# smopcb.net
KiCad netlist of a schematic drawn in EasyEDA
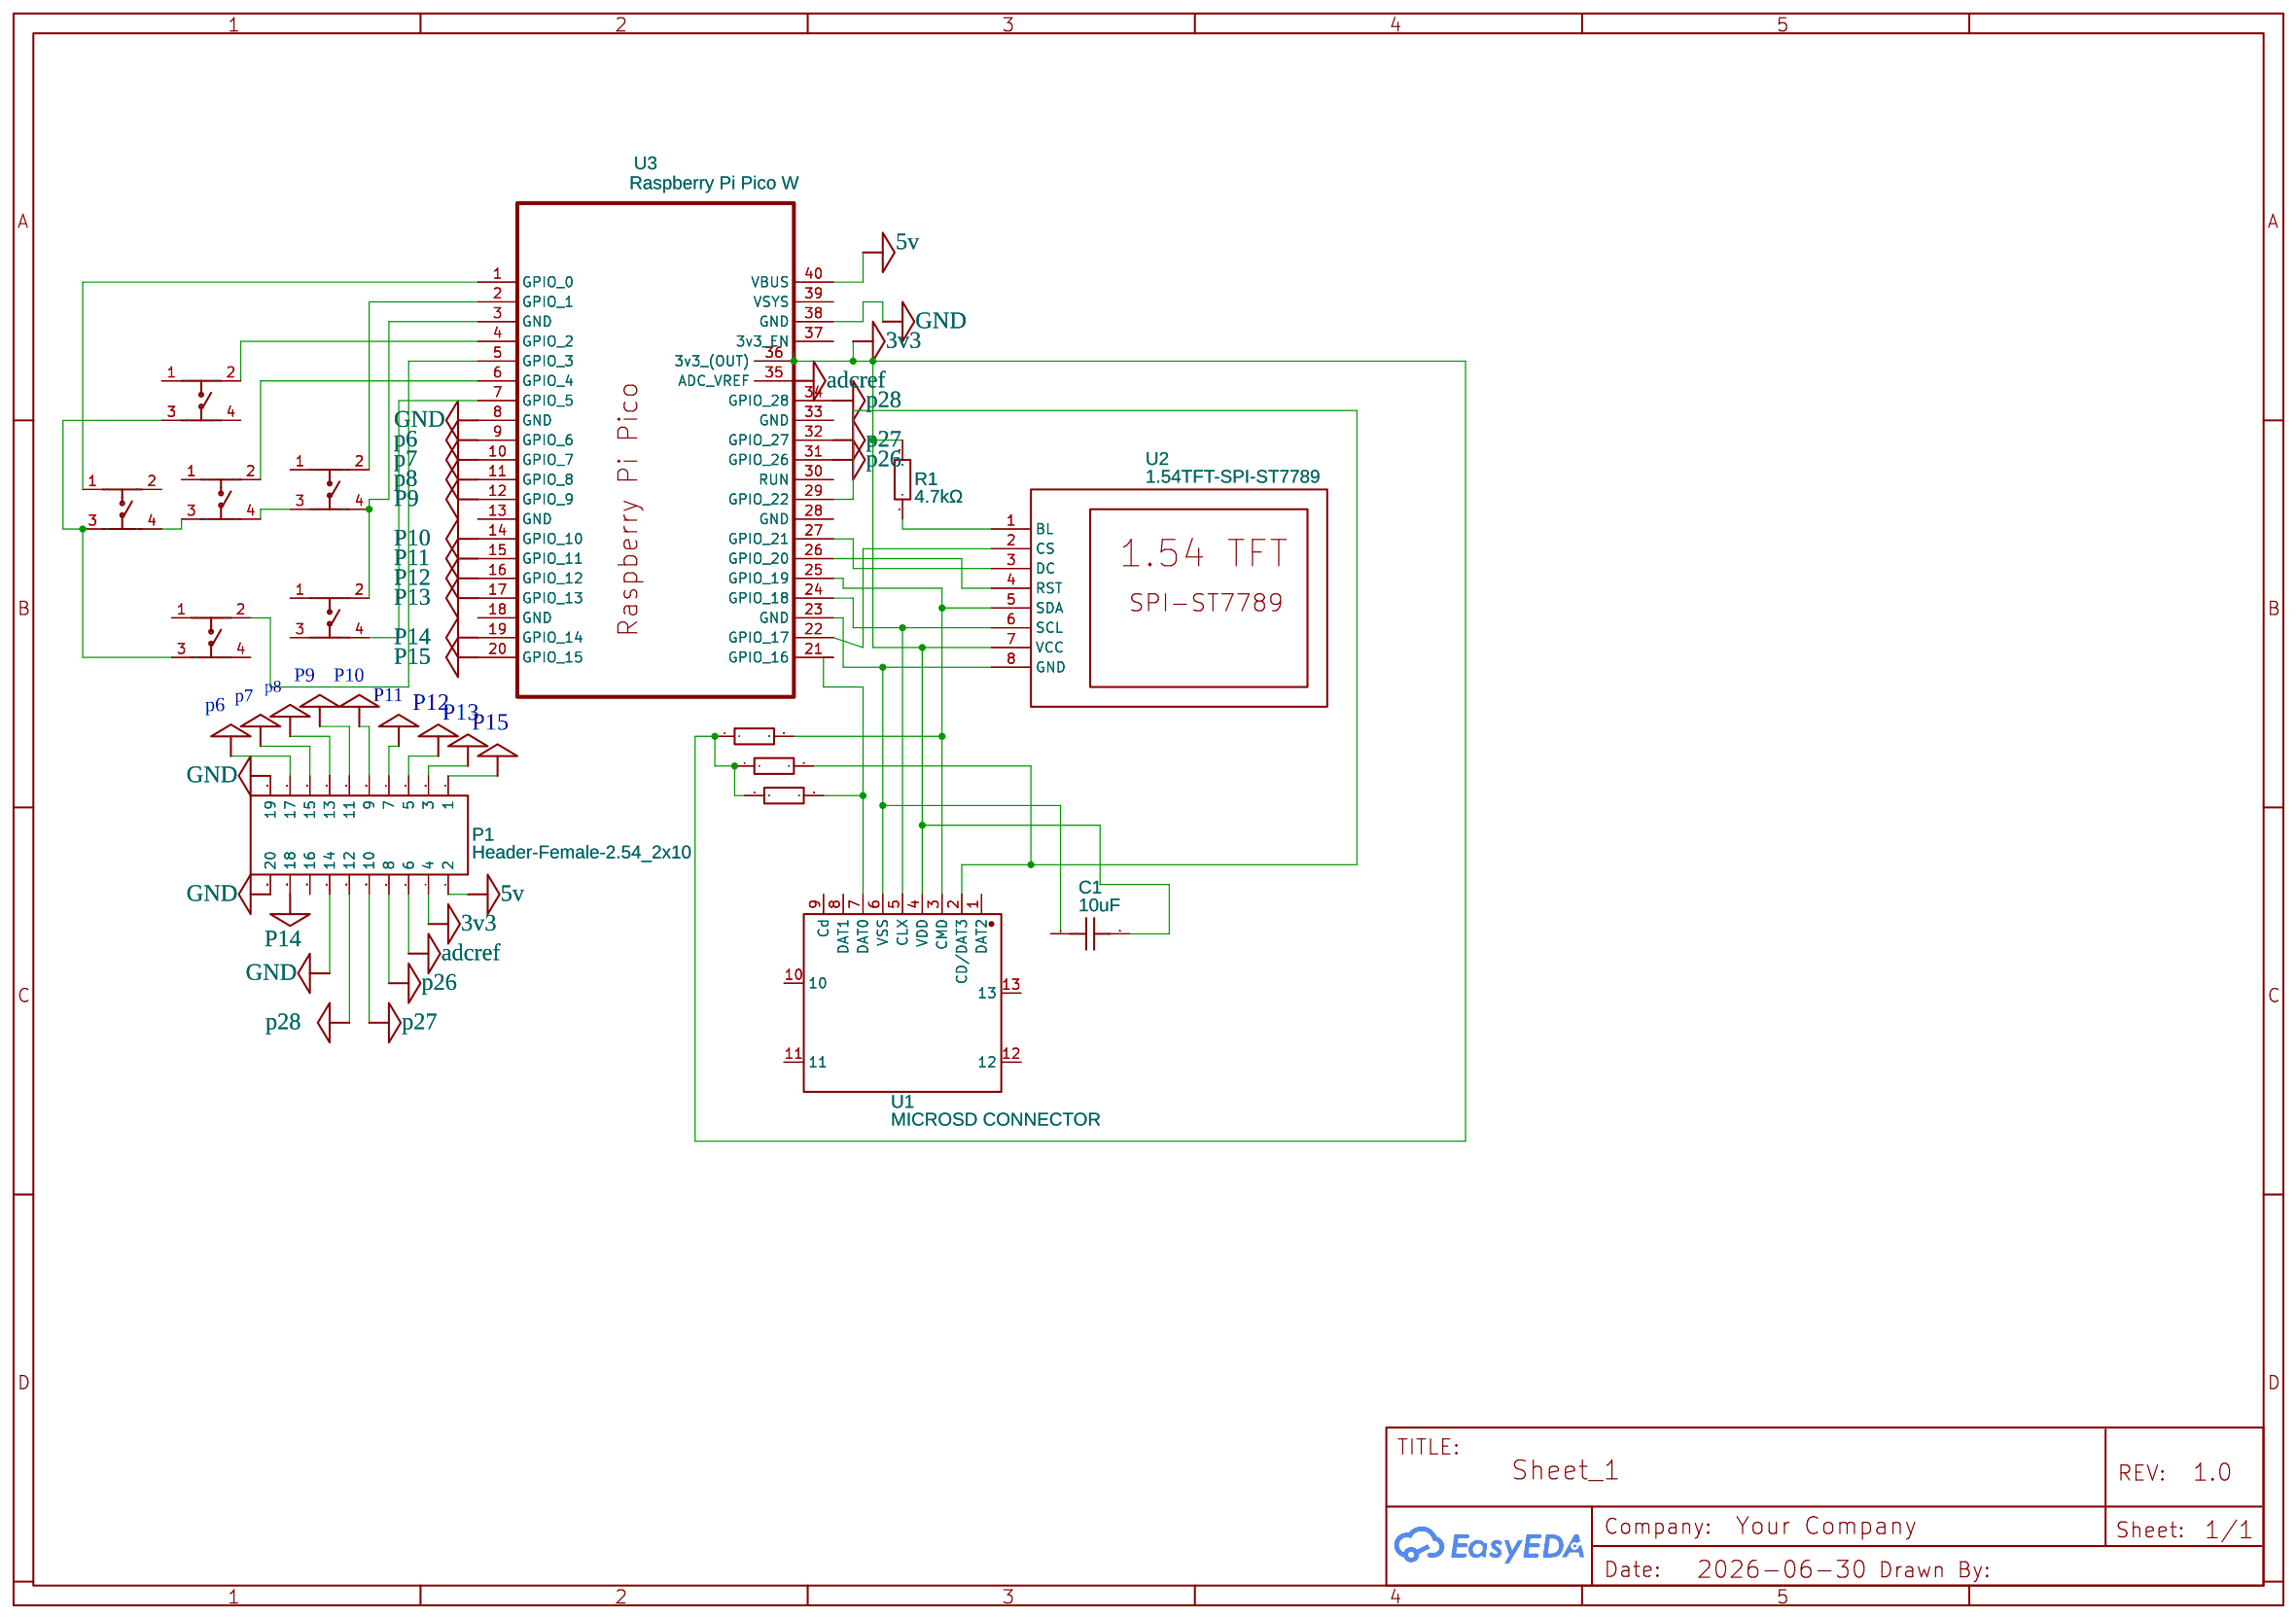
[diagram p0: schematic sheet]

(export (version "E")
  (design (tool "Eeschema 10.0.6"))
  (components
    (comp (ref "C1")
      (value "10uF")
      (fields
        (field (name "Manufacturer Part") "0805X5R106K350NT")
        (field (name "Manufacturer") "AIDE(爱迪电容)")
      )
      (libsource (lib "") (part "0805X5R106K350NT"))
    )
    (comp (ref "KEY1")
      (value "4PINTACTPCBTHTPUSHBUTTON")
      (fields (field (name "Manufacturer Part") "4pinTACTPCBTHTPushButton"))
      (libsource (lib "") (part "4PINTACTPCBTHTPUSHBUTTON"))
    )
    (comp (ref "KEY2")
      (value "4PINTACTPCBTHTPUSHBUTTON")
      (fields (field (name "Manufacturer Part") "4pinTACTPCBTHTPushButton"))
      (libsource (lib "") (part "4PINTACTPCBTHTPUSHBUTTON"))
    )
    (comp (ref "KEY3")
      (value "4PINTACTPCBTHTPUSHBUTTON")
      (fields (field (name "Manufacturer Part") "4pinTACTPCBTHTPushButton"))
      (libsource (lib "") (part "4PINTACTPCBTHTPUSHBUTTON"))
    )
    (comp (ref "KEY4")
      (value "4PINTACTPCBTHTPUSHBUTTON")
      (fields (field (name "Manufacturer Part") "4pinTACTPCBTHTPushButton"))
      (libsource (lib "") (part "4PINTACTPCBTHTPUSHBUTTON"))
    )
    (comp (ref "KEY5")
      (value "4PINTACTPCBTHTPUSHBUTTON")
      (fields (field (name "Manufacturer Part") "4pinTACTPCBTHTPushButton"))
      (libsource (lib "") (part "4PINTACTPCBTHTPUSHBUTTON"))
    )
    (comp (ref "KEY6")
      (value "4PINTACTPCBTHTPUSHBUTTON")
      (fields (field (name "Manufacturer Part") "4pinTACTPCBTHTPushButton"))
      (libsource (lib "") (part "4PINTACTPCBTHTPUSHBUTTON"))
    )
    (comp (ref "P1")
      (value "Header-Female-2.54_2x10")
      (fields (field (name "Manufacturer Part") "2.54-2*10P母") (field (name "Manufacturer") "BOOMELE(博穆精密)"))
      (libsource (lib "") (part "Header-Female-2.54_2x10"))
    )
    (comp (ref "R1")
      (value "4.7kΩ")
      (fields (field (name "Manufacturer Part") "RC0805FR-074K7L") (field (name "Manufacturer") "YAGEO(国巨)"))
      (libsource (lib "") (part "RESISTOR 0805 4K7"))
    )
    (comp (ref "R2")
      (value "4.7kΩ")
      (fields (field (name "Manufacturer Part") "RMC08054.7K1%N") (field (name "Manufacturer") "Tyohm(幸亚电阻)"))
      (libsource (lib "") (part "RMC08054.7K1%N"))
    )
    (comp (ref "R3")
      (value "4.7kΩ")
      (fields (field (name "Manufacturer Part") "RMC08054.7K1%N") (field (name "Manufacturer") "Tyohm(幸亚电阻)"))
      (libsource (lib "") (part "RMC08054.7K1%N"))
    )
    (comp (ref "R4")
      (value "4.7kΩ")
      (fields (field (name "Manufacturer Part") "RMC08054.7K1%N") (field (name "Manufacturer") "Tyohm(幸亚电阻)"))
      (libsource (lib "") (part "RMC08054.7K1%N"))
    )
    (comp (ref "U1")
      (value "MICROSD CONNECTOR")
      (fields (field (name "Manufacturer Part") "CQMicro_SDCARD_CQ036_HMA19PSMT"))
      (libsource (lib "") (part "MICROSD CONNECTOR"))
    )
    (comp (ref "U2") (value "1.54TFT-SPI-ST7789") (libsource (lib "") (part "1.54TFT-SPI-ST7789")))
    (comp (ref "U3") (value "Raspberry Pi Pico W") (libsource (lib "") (part "Raspberry Pi Pico W")))
  )
  (nets
    (net (code "1") (name "3v3") (class "Default")
      (node (ref "C1") (pin "2") (pinfunction "2_2") (pintype "unspecified"))
      (node (ref "P1") (pin "4") (pinfunction "4_4") (pintype "input"))
      (node (ref "R1") (pin "2") (pinfunction "2_2") (pintype "input"))
      (node (ref "R2") (pin "1") (pinfunction "1_1") (pintype "unspecified"))
      (node (ref "R3") (pin "1") (pinfunction "1_1") (pintype "unspecified"))
      (node (ref "R4") (pin "1") (pinfunction "1_1") (pintype "unspecified"))
      (node (ref "U1") (pin "4") (pinfunction "VDD_4") (pintype "unspecified"))
      (node (ref "U2") (pin "7") (pinfunction "VCC_7") (pintype "unspecified"))
      (node (ref "U3") (pin "36") (pinfunction "3v3_(OUT)_36") (pintype "unspecified"))
    )
    (net (code "2") (name "5v") (class "Default")
      (node (ref "P1") (pin "2") (pinfunction "2_2") (pintype "input"))
      (node (ref "U3") (pin "40") (pinfunction "VBUS_40") (pintype "unspecified"))
    )
    (net (code "3") (name "GND") (class "Default")
      (node (ref "P1") (pin "14") (pinfunction "14_14") (pintype "input"))
      (node (ref "P1") (pin "19") (pinfunction "19_19") (pintype "input"))
      (node (ref "P1") (pin "20") (pinfunction "20_20") (pintype "input"))
      (node (ref "U3") (pin "38") (pinfunction "GND_38") (pintype "unspecified"))
      (node (ref "U3") (pin "8") (pinfunction "GND_8") (pintype "unspecified"))
    )
    (net (code "4") (name "Net-(KEY1-Pad3)") (class "Default")
      (node (ref "KEY1") (pin "3") (pinfunction "3_3") (pintype "unspecified"))
      (node (ref "KEY2") (pin "3") (pinfunction "3_3") (pintype "unspecified"))
      (node (ref "KEY3") (pin "3") (pinfunction "3_3") (pintype "unspecified"))
    )
    (net (code "5") (name "Net-(KEY3-Pad4)") (class "Default")
      (node (ref "KEY3") (pin "4") (pinfunction "4_4") (pintype "unspecified"))
      (node (ref "KEY5") (pin "3") (pinfunction "3_3") (pintype "unspecified"))
    )
    (net (code "6") (name "Net-(KEY4-Pad3)") (class "Default")
      (node (ref "KEY4") (pin "3") (pinfunction "3_3") (pintype "unspecified"))
      (node (ref "KEY5") (pin "4") (pinfunction "4_4") (pintype "unspecified"))
    )
    (net (code "7") (name "Net-(KEY4-Pad4)") (class "Default")
      (node (ref "KEY4") (pin "4") (pinfunction "4_4") (pintype "unspecified"))
      (node (ref "KEY6") (pin "2") (pinfunction "2_2") (pintype "unspecified"))
      (node (ref "U3") (pin "3") (pinfunction "GND_3") (pintype "unspecified"))
    )
    (net (code "8") (name "Net-(U1-CD{slash}DAT3)") (class "Default")
      (node (ref "R2") (pin "2") (pinfunction "2_2") (pintype "unspecified"))
      (node (ref "U1") (pin "2") (pinfunction "CD/DAT3_2") (pintype "unspecified"))
      (node (ref "U3") (pin "29") (pinfunction "GPIO_22_29") (pintype "unspecified"))
    )
    (net (code "9") (name "Net-(U1-CLX)") (class "Default")
      (node (ref "U1") (pin "5") (pinfunction "CLX_5") (pintype "unspecified"))
      (node (ref "U2") (pin "6") (pinfunction "SCL_6") (pintype "unspecified"))
      (node (ref "U3") (pin "24") (pinfunction "GPIO_18_24") (pintype "unspecified"))
    )
    (net (code "10") (name "Net-(U1-CMD)") (class "Default")
      (node (ref "R4") (pin "2") (pinfunction "2_2") (pintype "unspecified"))
      (node (ref "U1") (pin "3") (pinfunction "CMD_3") (pintype "unspecified"))
      (node (ref "U2") (pin "5") (pinfunction "SDA_5") (pintype "unspecified"))
      (node (ref "U3") (pin "25") (pinfunction "GPIO_19_25") (pintype "unspecified"))
    )
    (net (code "11") (name "Net-(U1-DAT0)") (class "Default")
      (node (ref "R3") (pin "2") (pinfunction "2_2") (pintype "unspecified"))
      (node (ref "U1") (pin "7") (pinfunction "DAT0_7") (pintype "unspecified"))
      (node (ref "U3") (pin "21") (pinfunction "GPIO_16_21") (pintype "unspecified"))
    )
    (net (code "12") (name "Net-(U1-VSS)") (class "Default")
      (node (ref "C1") (pin "1") (pinfunction "1_1") (pintype "unspecified"))
      (node (ref "U1") (pin "6") (pinfunction "VSS_6") (pintype "unspecified"))
      (node (ref "U2") (pin "8") (pinfunction "GND_8") (pintype "unspecified"))
      (node (ref "U3") (pin "23") (pinfunction "GND_23") (pintype "unspecified"))
    )
    (net (code "13") (name "Net-(U2-BL)") (class "Default")
      (node (ref "R1") (pin "1") (pinfunction "1_1") (pintype "input"))
      (node (ref "U2") (pin "1") (pinfunction "BL_1") (pintype "unspecified"))
    )
    (net (code "14") (name "Net-(U2-CS)") (class "Default")
      (node (ref "U2") (pin "2") (pinfunction "CS_2") (pintype "unspecified"))
      (node (ref "U3") (pin "22") (pinfunction "GPIO_17_22") (pintype "unspecified"))
    )
    (net (code "15") (name "Net-(U2-DC)") (class "Default")
      (node (ref "U2") (pin "3") (pinfunction "DC_3") (pintype "unspecified"))
      (node (ref "U3") (pin "27") (pinfunction "GPIO_21_27") (pintype "unspecified"))
    )
    (net (code "16") (name "Net-(U2-RST)") (class "Default")
      (node (ref "U2") (pin "4") (pinfunction "RST_4") (pintype "unspecified"))
      (node (ref "U3") (pin "26") (pinfunction "GPIO_20_26") (pintype "unspecified"))
    )
    (net (code "17") (name "Net-(U3-GPIO_0)") (class "Default")
      (node (ref "KEY3") (pin "1") (pinfunction "1_1") (pintype "unspecified"))
      (node (ref "U3") (pin "1") (pinfunction "GPIO_0_1") (pintype "unspecified"))
    )
    (net (code "18") (name "Net-(U3-GPIO_1)") (class "Default")
      (node (ref "KEY4") (pin "2") (pinfunction "2_2") (pintype "unspecified"))
      (node (ref "U3") (pin "2") (pinfunction "GPIO_1_2") (pintype "unspecified"))
    )
    (net (code "19") (name "Net-(U3-GPIO_2)") (class "Default")
      (node (ref "KEY1") (pin "2") (pinfunction "2_2") (pintype "unspecified"))
      (node (ref "U3") (pin "4") (pinfunction "GPIO_2_4") (pintype "unspecified"))
    )
    (net (code "20") (name "Net-(U3-GPIO_3)") (class "Default")
      (node (ref "KEY2") (pin "2") (pinfunction "2_2") (pintype "unspecified"))
      (node (ref "U3") (pin "5") (pinfunction "GPIO_3_5") (pintype "unspecified"))
    )
    (net (code "21") (name "Net-(U3-GPIO_4)") (class "Default")
      (node (ref "KEY5") (pin "2") (pinfunction "2_2") (pintype "unspecified"))
      (node (ref "U3") (pin "6") (pinfunction "GPIO_4_6") (pintype "unspecified"))
    )
    (net (code "22") (name "Net-(U3-GPIO_5)") (class "Default")
      (node (ref "KEY6") (pin "4") (pinfunction "4_4") (pintype "unspecified"))
      (node (ref "U3") (pin "7") (pinfunction "GPIO_5_7") (pintype "unspecified"))
    )
    (net (code "23") (name "P9") (class "Default")
      (node (ref "P1") (pin "11") (pinfunction "11_11") (pintype "input"))
      (node (ref "U3") (pin "12") (pinfunction "GPIO_9_12") (pintype "unspecified"))
    )
    (net (code "24") (name "P10") (class "Default")
      (node (ref "P1") (pin "9") (pinfunction "9_9") (pintype "input"))
      (node (ref "U3") (pin "14") (pinfunction "GPIO_10_14") (pintype "unspecified"))
    )
    (net (code "25") (name "P11") (class "Default")
      (node (ref "P1") (pin "7") (pinfunction "7_7") (pintype "input"))
      (node (ref "U3") (pin "15") (pinfunction "GPIO_11_15") (pintype "unspecified"))
    )
    (net (code "26") (name "P12") (class "Default")
      (node (ref "P1") (pin "5") (pinfunction "5_5") (pintype "input"))
      (node (ref "U3") (pin "16") (pinfunction "GPIO_12_16") (pintype "unspecified"))
    )
    (net (code "27") (name "P13") (class "Default")
      (node (ref "P1") (pin "3") (pinfunction "3_3") (pintype "input"))
      (node (ref "U3") (pin "17") (pinfunction "GPIO_13_17") (pintype "unspecified"))
    )
    (net (code "28") (name "P14") (class "Default")
      (node (ref "P1") (pin "18") (pinfunction "18_18") (pintype "input"))
      (node (ref "U3") (pin "19") (pinfunction "GPIO_14_19") (pintype "unspecified"))
    )
    (net (code "29") (name "P15") (class "Default")
      (node (ref "P1") (pin "1") (pinfunction "1_1") (pintype "input"))
      (node (ref "U3") (pin "20") (pinfunction "GPIO_15_20") (pintype "unspecified"))
    )
    (net (code "30") (name "adcref") (class "Default")
      (node (ref "P1") (pin "6") (pinfunction "6_6") (pintype "input"))
      (node (ref "U3") (pin "35") (pinfunction "ADC_VREF_35") (pintype "unspecified"))
    )
    (net (code "31") (name "p6") (class "Default")
      (node (ref "P1") (pin "17") (pinfunction "17_17") (pintype "input"))
      (node (ref "U3") (pin "9") (pinfunction "GPIO_6_9") (pintype "unspecified"))
    )
    (net (code "32") (name "p7") (class "Default")
      (node (ref "P1") (pin "15") (pinfunction "15_15") (pintype "input"))
      (node (ref "U3") (pin "10") (pinfunction "GPIO_7_10") (pintype "unspecified"))
    )
    (net (code "33") (name "p8") (class "Default")
      (node (ref "P1") (pin "13") (pinfunction "13_13") (pintype "input"))
      (node (ref "U3") (pin "11") (pinfunction "GPIO_8_11") (pintype "unspecified"))
    )
    (net (code "34") (name "p26") (class "Default")
      (node (ref "P1") (pin "8") (pinfunction "8_8") (pintype "input"))
      (node (ref "U3") (pin "31") (pinfunction "GPIO_26_31") (pintype "unspecified"))
    )
    (net (code "35") (name "p27") (class "Default")
      (node (ref "P1") (pin "10") (pinfunction "10_10") (pintype "input"))
      (node (ref "U3") (pin "32") (pinfunction "GPIO_27_32") (pintype "unspecified"))
    )
    (net (code "36") (name "p28") (class "Default")
      (node (ref "P1") (pin "12") (pinfunction "12_12") (pintype "input"))
      (node (ref "U3") (pin "34") (pinfunction "GPIO_28_34") (pintype "unspecified"))
    )
    (net (code "37") (name "unconnected-(KEY1-Pad1)") (class "Default")
      (node (ref "KEY1") (pin "1") (pinfunction "1_1") (pintype "unspecified"))
    )
    (net (code "38") (name "unconnected-(KEY1-Pad4)") (class "Default")
      (node (ref "KEY1") (pin "4") (pinfunction "4_4") (pintype "unspecified"))
    )
    (net (code "39") (name "unconnected-(KEY2-Pad1)") (class "Default")
      (node (ref "KEY2") (pin "1") (pinfunction "1_1") (pintype "unspecified"))
    )
    (net (code "40") (name "unconnected-(KEY2-Pad4)") (class "Default")
      (node (ref "KEY2") (pin "4") (pinfunction "4_4") (pintype "unspecified"))
    )
    (net (code "41") (name "unconnected-(KEY3-Pad2)") (class "Default")
      (node (ref "KEY3") (pin "2") (pinfunction "2_2") (pintype "unspecified"))
    )
    (net (code "42") (name "unconnected-(KEY4-Pad1)") (class "Default")
      (node (ref "KEY4") (pin "1") (pinfunction "1_1") (pintype "unspecified"))
    )
    (net (code "43") (name "unconnected-(KEY5-Pad1)") (class "Default")
      (node (ref "KEY5") (pin "1") (pinfunction "1_1") (pintype "unspecified"))
    )
    (net (code "44") (name "unconnected-(KEY6-Pad1)") (class "Default")
      (node (ref "KEY6") (pin "1") (pinfunction "1_1") (pintype "unspecified"))
    )
    (net (code "45") (name "unconnected-(KEY6-Pad3)") (class "Default")
      (node (ref "KEY6") (pin "3") (pinfunction "3_3") (pintype "unspecified"))
    )
    (net (code "46") (name "unconnected-(P1-Pad16)") (class "Default")
      (node (ref "P1") (pin "16") (pinfunction "16_16") (pintype "input"))
    )
    (net (code "47") (name "unconnected-(U1-Cd-Pad9)") (class "Default")
      (node (ref "U1") (pin "9") (pinfunction "Cd_9") (pintype "unspecified"))
    )
    (net (code "48") (name "unconnected-(U1-DAT1-Pad8)") (class "Default")
      (node (ref "U1") (pin "8") (pinfunction "DAT1_8") (pintype "unspecified"))
    )
    (net (code "49") (name "unconnected-(U1-DAT2-Pad1)") (class "Default")
      (node (ref "U1") (pin "1") (pinfunction "DAT2_1") (pintype "unspecified"))
    )
    (net (code "50") (name "unconnected-(U1-Pad10)") (class "Default")
      (node (ref "U1") (pin "10") (pinfunction "10_10") (pintype "unspecified"))
    )
    (net (code "51") (name "unconnected-(U1-Pad11)") (class "Default")
      (node (ref "U1") (pin "11") (pinfunction "11_11") (pintype "unspecified"))
    )
    (net (code "52") (name "unconnected-(U1-Pad12)") (class "Default")
      (node (ref "U1") (pin "12") (pinfunction "12_12") (pintype "unspecified"))
    )
    (net (code "53") (name "unconnected-(U1-Pad13)") (class "Default")
      (node (ref "U1") (pin "13") (pinfunction "13_13") (pintype "unspecified"))
    )
    (net (code "54") (name "unconnected-(U3-3v3_EN-Pad37)") (class "Default")
      (node (ref "U3") (pin "37") (pinfunction "3v3_EN_37") (pintype "unspecified"))
    )
    (net (code "55") (name "unconnected-(U3-GND-Pad13)") (class "Default")
      (node (ref "U3") (pin "13") (pinfunction "GND_13") (pintype "unspecified"))
    )
    (net (code "56") (name "unconnected-(U3-GND-Pad18)") (class "Default")
      (node (ref "U3") (pin "18") (pinfunction "GND_18") (pintype "unspecified"))
    )
    (net (code "57") (name "unconnected-(U3-GND-Pad28)") (class "Default")
      (node (ref "U3") (pin "28") (pinfunction "GND_28") (pintype "unspecified"))
    )
    (net (code "58") (name "unconnected-(U3-GND-Pad33)") (class "Default")
      (node (ref "U3") (pin "33") (pinfunction "GND_33") (pintype "unspecified"))
    )
    (net (code "59") (name "unconnected-(U3-RUN-Pad30)") (class "Default")
      (node (ref "U3") (pin "30") (pinfunction "RUN_30") (pintype "unspecified"))
    )
    (net (code "60") (name "unconnected-(U3-VSYS-Pad39)") (class "Default")
      (node (ref "U3") (pin "39") (pinfunction "VSYS_39") (pintype "unspecified"))
    )
  )
)
